# cpu.net
KiCad netlist of a schematic drawn in Altium Designer
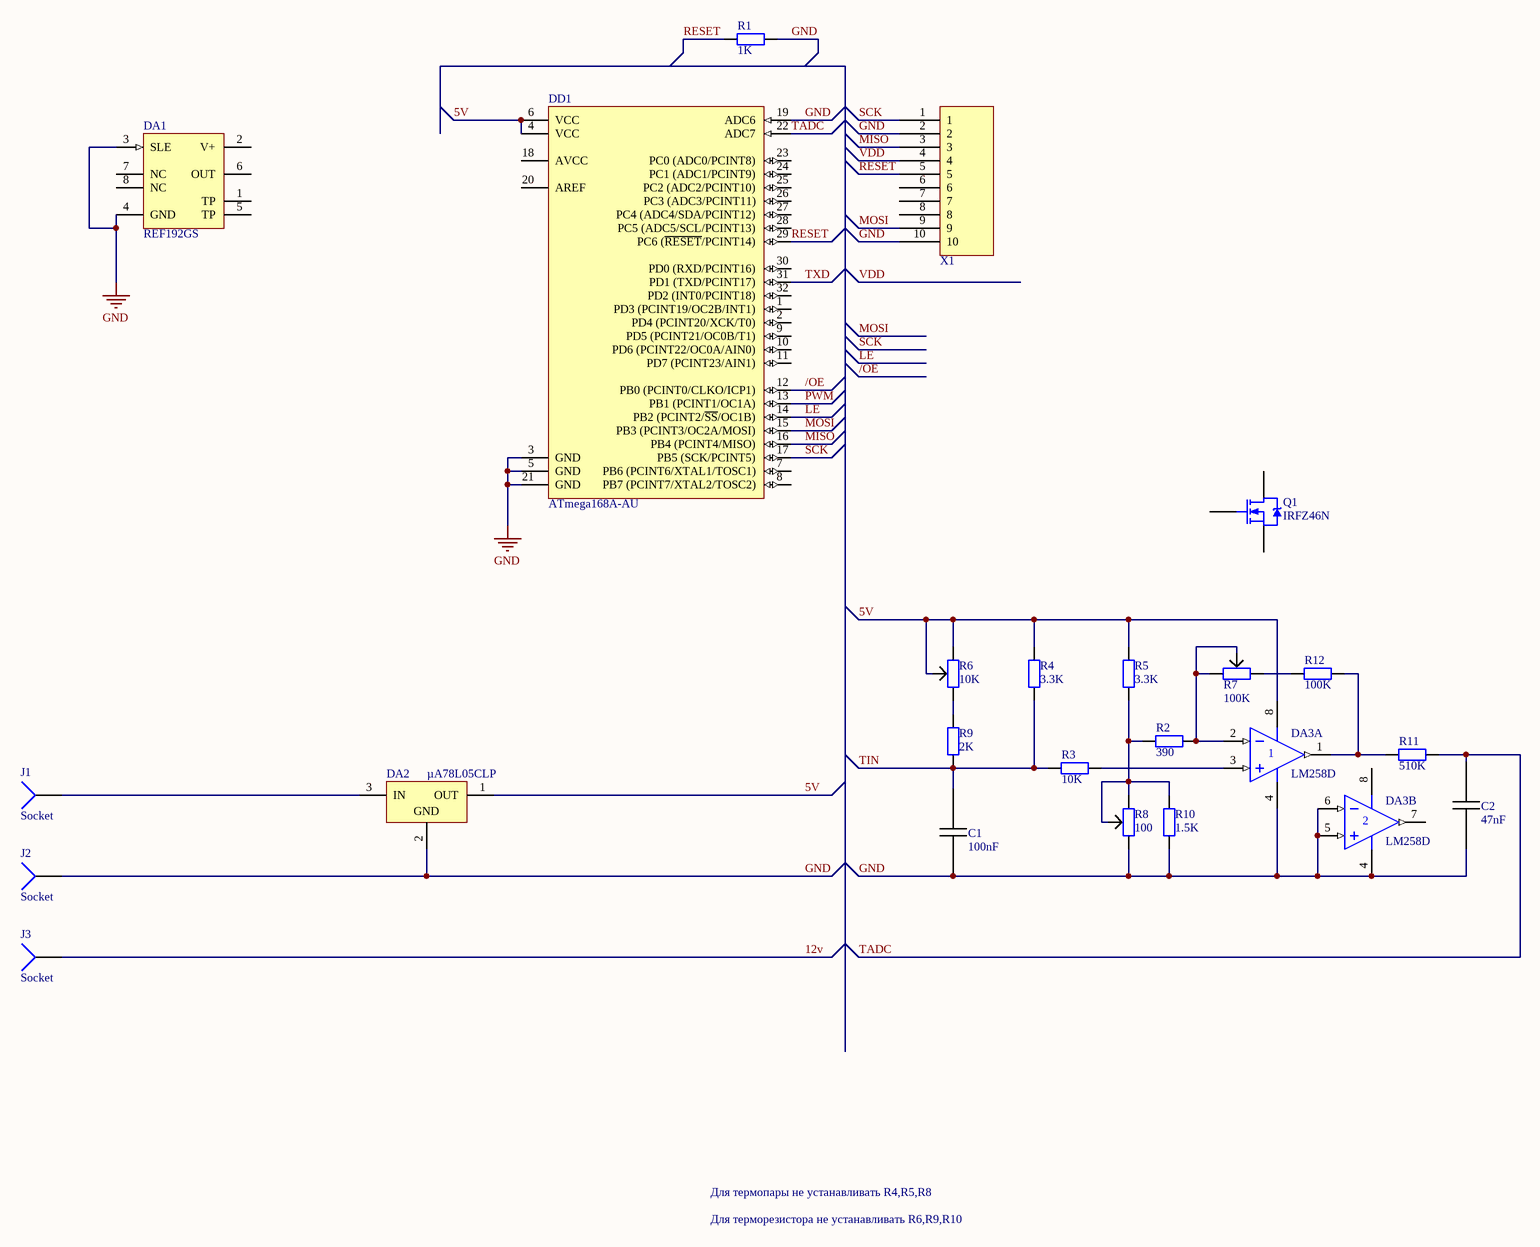
[diagram p0: cpu.SchDoc]

(export (version "E")
  (design (tool "Eeschema 10.0.6"))
  (components
    (comp (ref "C1") (value "100nF") (footprint "R1206") (libsource (lib "Schlib1") (part "cap")))
    (comp (ref "C2") (value "47nF") (footprint "R1206") (libsource (lib "Schlib1") (part "cap")))
    (comp (ref "DA1")
      (value "REF192GS")
      (footprint "SO-8_N")
      (description "2.50V, Precision Micropower, Low-Dropout, Voltage Reference")
      (fields (field (name "PUBLISHER") "Altium Limited"))
      (libsource (lib "AD Power Mgt Voltage Reference") (part "REF192GS"))
    )
    (comp (ref "DA2")
      (value "µA78L05CLP")
      (footprint "LP03")
      (description "Positive-Voltage Regulator")
      (fields (field (name "PUBLISHER") "Altium Limited"))
      (libsource (lib "TI Power Mgt Voltage Regulator") (part "µA78L05CLP"))
    )
    (comp (ref "DA3")
      (value "LM258D")
      (footprint "D008_L")
      (description "Dual Operational Amplifier")
      (fields (field (name "PUBLISHER") "Altium Limited"))
      (libsource (lib "TI Operational Amplifier") (part "LM258D"))
    )
    (comp (ref "DD1")
      (value "ATmega168A-AU")
      (footprint "32A_N")
      (fields (field (name "PUBLISHER") "Altium Limited"))
      (libsource (lib "Atmel Microcontroller 8-Bit megaAVR") (part "ATmega168A-AU"))
    )
    (comp (ref "J1")
      (value "Socket")
      (footprint "PIN1")
      (fields (field (name "PUBLISHER") "Altium Limited"))
      (libsource (lib "Miscellaneous Connectors") (part "Socket"))
    )
    (comp (ref "J2")
      (value "Socket")
      (footprint "PIN1")
      (fields (field (name "PUBLISHER") "Altium Limited"))
      (libsource (lib "Miscellaneous Connectors") (part "Socket"))
    )
    (comp (ref "J3")
      (value "Socket")
      (footprint "PIN1")
      (fields (field (name "PUBLISHER") "Altium Limited"))
      (libsource (lib "Miscellaneous Connectors") (part "Socket"))
    )
    (comp (ref "Q1")
      (value "IRFZ46N")
      (footprint "TO-220AB")
      (description "HEXFET Power MOSFET")
      (fields (field (name "PUBLISHER") "Altium Limited"))
      (libsource (lib "IR Discrete MOSFET - Power") (part "IRFZ46N"))
    )
    (comp (ref "R1") (value "1K") (footprint "PcbLib1:R1206") (libsource (lib "Schlib1") (part "Res")))
    (comp (ref "R2") (value "390") (footprint "PcbLib1:R1206") (libsource (lib "Schlib1") (part "Res")))
    (comp (ref "R3") (value "10K") (footprint "PcbLib1:R1206") (libsource (lib "Schlib1") (part "Res")))
    (comp (ref "R4") (value "3.3K") (footprint "PcbLib1:R1206") (libsource (lib "") (part "Res_2")))
    (comp (ref "R5") (value "3.3K") (footprint "PcbLib1:R1206") (libsource (lib "") (part "Res_2")))
    (comp (ref "R6") (value "10K") (footprint "3296x") (libsource (lib "") (part "RES_P_1")))
    (comp (ref "R7") (value "100K") (footprint "3296x") (libsource (lib "Schlib1") (part "RES_P")))
    (comp (ref "R8") (value "100") (footprint "3296x") (libsource (lib "") (part "RES_P_1")))
    (comp (ref "R9") (value "2K") (footprint "PcbLib1:R1206") (libsource (lib "") (part "Res_2")))
    (comp (ref "R10") (value "1.5K") (footprint "PcbLib1:R1206") (libsource (lib "") (part "Res_2")))
    (comp (ref "R11") (value "510K") (footprint "PcbLib1:R1206") (libsource (lib "") (part "Res_1")))
    (comp (ref "R12") (value "100K") (footprint "PcbLib1:R1206") (libsource (lib "") (part "Res_1")))
    (comp (ref "X1") (value "BHS-10") (footprint "BHS-10") (libsource (lib "Schlib1") (part "BHS-10")))
  )
  (nets
    (net (code "1") (name "/5V") (class "Default")
      (node (ref "DA2") (pin "1") (pinfunction "OUT_1") (pintype "power_in"))
      (node (ref "DA3") (pin "8") (pinfunction "V+_8") (pintype "power_in"))
      (node (ref "DD1") (pin "4") (pinfunction "VCC_4") (pintype "power_in"))
      (node (ref "DD1") (pin "6") (pinfunction "VCC_6") (pintype "power_in"))
      (node (ref "R4") (pin "2") (pinfunction "2_2") (pintype "passive"))
      (node (ref "R5") (pin "2") (pinfunction "2_2") (pintype "passive"))
      (node (ref "R6") (pin "2") (pinfunction "2_2") (pintype "passive"))
      (node (ref "R6") (pin "3") (pinfunction "3_3") (pintype "passive"))
    )
    (net (code "2") (name "/12v") (class "Default")
      (node (ref "J3") (pin "1") (pinfunction "1_1") (pintype "passive"))
    )
    (net (code "3") (name "/LE") (class "Default")
      (node (ref "DD1") (pin "14") (pinfunction "PB2_(PCINT2/~{SS}/OC1B)_14") (pintype "bidirectional"))
    )
    (net (code "4") (name "/MISO") (class "Default")
      (node (ref "DD1") (pin "16") (pinfunction "PB4_(PCINT4/MISO)_16") (pintype "bidirectional"))
      (node (ref "X1") (pin "3") (pinfunction "3_3") (pintype "passive"))
    )
    (net (code "5") (name "/MOSI") (class "Default")
      (node (ref "DD1") (pin "15") (pinfunction "PB3_(PCINT3/OC2A/MOSI)_15") (pintype "bidirectional"))
      (node (ref "X1") (pin "9") (pinfunction "9_9") (pintype "passive"))
    )
    (net (code "6") (name "/PWM") (class "Default")
      (node (ref "DD1") (pin "13") (pinfunction "PB1_(PCINT1/OC1A)_13") (pintype "bidirectional"))
    )
    (net (code "7") (name "/RESET") (class "Default")
      (node (ref "DD1") (pin "29") (pinfunction "PC6_(~{RESET}/PCINT14)_29") (pintype "bidirectional"))
      (node (ref "R1") (pin "1") (pinfunction "1_1") (pintype "passive"))
      (node (ref "X1") (pin "5") (pinfunction "5_5") (pintype "passive"))
    )
    (net (code "8") (name "/SCK") (class "Default")
      (node (ref "DD1") (pin "17") (pinfunction "PB5_(SCK/PCINT5)_17") (pintype "bidirectional"))
      (node (ref "X1") (pin "1") (pinfunction "1_1") (pintype "passive"))
    )
    (net (code "9") (name "/TADC") (class "Default")
      (node (ref "C2") (pin "2") (pinfunction "2_2") (pintype "passive"))
      (node (ref "DD1") (pin "22") (pinfunction "ADC7_22") (pintype "input"))
      (node (ref "R11") (pin "1") (pinfunction "1_1") (pintype "passive"))
    )
    (net (code "10") (name "/TIN") (class "Default")
      (node (ref "C1") (pin "2") (pinfunction "2_2") (pintype "passive"))
      (node (ref "R3") (pin "1") (pinfunction "1_1") (pintype "passive"))
      (node (ref "R4") (pin "1") (pinfunction "1_1") (pintype "passive"))
      (node (ref "R9") (pin "1") (pinfunction "1_1") (pintype "passive"))
    )
    (net (code "11") (name "/TXD") (class "Default")
      (node (ref "DD1") (pin "31") (pinfunction "PD1_(TXD/PCINT17)_31") (pintype "bidirectional"))
    )
    (net (code "12") (name "/VDD") (class "Default")
      (node (ref "X1") (pin "4") (pinfunction "4_4") (pintype "passive"))
    )
    (net (code "13") (name "/{slash}OE") (class "Default")
      (node (ref "DD1") (pin "12") (pinfunction "PB0_(PCINT0/CLKO/ICP1)_12") (pintype "bidirectional"))
    )
    (net (code "14") (name "GND") (class "Default")
      (node (ref "C1") (pin "1") (pinfunction "1_1") (pintype "passive"))
      (node (ref "C2") (pin "1") (pinfunction "1_1") (pintype "passive"))
      (node (ref "DA1") (pin "3") (pinfunction "SLE_3") (pintype "input"))
      (node (ref "DA1") (pin "4") (pinfunction "GND_4") (pintype "power_in"))
      (node (ref "DA2") (pin "2") (pinfunction "GND_2") (pintype "power_in"))
      (node (ref "DA3") (pin "4") (pinfunction "V-_4") (pintype "power_in"))
      (node (ref "DA3") (pin "5") (pinfunction "IN+_5") (pintype "input"))
      (node (ref "DA3") (pin "6") (pinfunction "IN-_6") (pintype "input"))
      (node (ref "DD1") (pin "19") (pinfunction "ADC6_19") (pintype "input"))
      (node (ref "DD1") (pin "21") (pinfunction "GND_21") (pintype "power_in"))
      (node (ref "DD1") (pin "3") (pinfunction "GND_3") (pintype "power_in"))
      (node (ref "DD1") (pin "5") (pinfunction "GND_5") (pintype "power_in"))
      (node (ref "J2") (pin "1") (pinfunction "1_1") (pintype "passive"))
      (node (ref "R1") (pin "2") (pinfunction "2_2") (pintype "passive"))
      (node (ref "R10") (pin "1") (pinfunction "1_1") (pintype "passive"))
      (node (ref "R8") (pin "1") (pinfunction "1_1") (pintype "passive"))
      (node (ref "X1") (pin "10") (pinfunction "10_10") (pintype "passive"))
      (node (ref "X1") (pin "2") (pinfunction "2_2") (pintype "passive"))
    )
    (net (code "15") (name "Net-(DA2-IN)") (class "Default")
      (node (ref "DA2") (pin "3") (pinfunction "IN_3") (pintype "power_in"))
      (node (ref "J1") (pin "1") (pinfunction "1_1") (pintype "passive"))
    )
    (net (code "16") (name "Net-(DA3A-IN+)") (class "Default")
      (node (ref "DA3") (pin "3") (pinfunction "IN+_3") (pintype "input"))
      (node (ref "R3") (pin "2") (pinfunction "2_2") (pintype "passive"))
    )
    (net (code "17") (name "Net-(DA3A-IN-)") (class "Default")
      (node (ref "DA3") (pin "2") (pinfunction "IN-_2") (pintype "input"))
      (node (ref "R2") (pin "2") (pinfunction "2_2") (pintype "passive"))
      (node (ref "R7") (pin "1") (pinfunction "1_1") (pintype "passive"))
      (node (ref "R7") (pin "2") (pinfunction "2_2") (pintype "passive"))
    )
    (net (code "18") (name "Net-(DA3A-OUT)") (class "Default")
      (node (ref "DA3") (pin "1") (pinfunction "OUT_1") (pintype "output"))
      (node (ref "R11") (pin "2") (pinfunction "2_2") (pintype "passive"))
      (node (ref "R12") (pin "1") (pinfunction "1_1") (pintype "passive"))
    )
    (net (code "19") (name "Net-(R6-Pad1)") (class "Default")
      (node (ref "R6") (pin "1") (pinfunction "1_1") (pintype "passive"))
      (node (ref "R9") (pin "2") (pinfunction "2_2") (pintype "passive"))
    )
    (net (code "20") (name "Net-(R10-Pad2)") (class "Default")
      (node (ref "R10") (pin "2") (pinfunction "2_2") (pintype "passive"))
      (node (ref "R2") (pin "1") (pinfunction "1_1") (pintype "passive"))
      (node (ref "R5") (pin "1") (pinfunction "1_1") (pintype "passive"))
      (node (ref "R8") (pin "2") (pinfunction "2_2") (pintype "passive"))
      (node (ref "R8") (pin "3") (pinfunction "3_3") (pintype "passive"))
    )
    (net (code "21") (name "Net-(R12-Pad2)") (class "Default")
      (node (ref "R12") (pin "2") (pinfunction "2_2") (pintype "passive"))
      (node (ref "R7") (pin "3") (pinfunction "3_3") (pintype "passive"))
    )
    (net (code "22") (name "unconnected-(DA1-NC-Pad7)") (class "Default")
      (node (ref "DA1") (pin "7") (pinfunction "NC_7") (pintype "passive"))
    )
    (net (code "23") (name "unconnected-(DA1-NC-Pad8)") (class "Default")
      (node (ref "DA1") (pin "8") (pinfunction "NC_8") (pintype "passive"))
    )
    (net (code "24") (name "unconnected-(DA1-OUT-Pad6)") (class "Default")
      (node (ref "DA1") (pin "6") (pinfunction "OUT_6") (pintype "power_in"))
    )
    (net (code "25") (name "unconnected-(DA1-TP-Pad1)") (class "Default")
      (node (ref "DA1") (pin "1") (pinfunction "TP_1") (pintype "passive"))
    )
    (net (code "26") (name "unconnected-(DA1-TP-Pad5)") (class "Default")
      (node (ref "DA1") (pin "5") (pinfunction "TP_5") (pintype "passive"))
    )
    (net (code "27") (name "unconnected-(DA1-V+-Pad2)") (class "Default")
      (node (ref "DA1") (pin "2") (pinfunction "V+_2") (pintype "power_in"))
    )
    (net (code "28") (name "unconnected-(DA3B-OUT-Pad7)") (class "Default")
      (node (ref "DA3") (pin "7") (pinfunction "OUT_7") (pintype "output"))
    )
    (net (code "29") (name "unconnected-(DA3B-V+-Pad8)") (class "Default")
      (node (ref "DA3") (pin "8") (pinfunction "V+_8") (pintype "power_in"))
    )
    (net (code "30") (name "unconnected-(DD1-AREF-Pad20)") (class "Default")
      (node (ref "DD1") (pin "20") (pinfunction "AREF_20") (pintype "passive"))
    )
    (net (code "31") (name "unconnected-(DD1-AVCC-Pad18)") (class "Default")
      (node (ref "DD1") (pin "18") (pinfunction "AVCC_18") (pintype "power_in"))
    )
    (net (code "32") (name "unconnected-(DD1-PB6_(PCINT6{slash}XTAL1{slash}TOSC1)-Pad7)") (class "Default")
      (node (ref "DD1") (pin "7") (pinfunction "PB6_(PCINT6/XTAL1/TOSC1)_7") (pintype "bidirectional"))
    )
    (net (code "33") (name "unconnected-(DD1-PB7_(PCINT7{slash}XTAL2{slash}TOSC2)-Pad8)") (class "Default")
      (node (ref "DD1") (pin "8") (pinfunction "PB7_(PCINT7/XTAL2/TOSC2)_8") (pintype "bidirectional"))
    )
    (net (code "34") (name "unconnected-(DD1-PC0_(ADC0{slash}PCINT8)-Pad23)") (class "Default")
      (node (ref "DD1") (pin "23") (pinfunction "PC0_(ADC0/PCINT8)_23") (pintype "bidirectional"))
    )
    (net (code "35") (name "unconnected-(DD1-PC1_(ADC1{slash}PCINT9)-Pad24)") (class "Default")
      (node (ref "DD1") (pin "24") (pinfunction "PC1_(ADC1/PCINT9)_24") (pintype "bidirectional"))
    )
    (net (code "36") (name "unconnected-(DD1-PC2_(ADC2{slash}PCINT10)-Pad25)") (class "Default")
      (node (ref "DD1") (pin "25") (pinfunction "PC2_(ADC2/PCINT10)_25") (pintype "bidirectional"))
    )
    (net (code "37") (name "unconnected-(DD1-PC3_(ADC3{slash}PCINT11)-Pad26)") (class "Default")
      (node (ref "DD1") (pin "26") (pinfunction "PC3_(ADC3/PCINT11)_26") (pintype "bidirectional"))
    )
    (net (code "38") (name "unconnected-(DD1-PC4_(ADC4{slash}SDA{slash}PCINT12)-Pad27)") (class "Default")
      (node (ref "DD1") (pin "27") (pinfunction "PC4_(ADC4/SDA/PCINT12)_27") (pintype "bidirectional"))
    )
    (net (code "39") (name "unconnected-(DD1-PC5_(ADC5{slash}SCL{slash}PCINT13)-Pad28)") (class "Default")
      (node (ref "DD1") (pin "28") (pinfunction "PC5_(ADC5/SCL/PCINT13)_28") (pintype "bidirectional"))
    )
    (net (code "40") (name "unconnected-(DD1-PD0_(RXD{slash}PCINT16)-Pad30)") (class "Default")
      (node (ref "DD1") (pin "30") (pinfunction "PD0_(RXD/PCINT16)_30") (pintype "bidirectional"))
    )
    (net (code "41") (name "unconnected-(DD1-PD2_(INT0{slash}PCINT18)-Pad32)") (class "Default")
      (node (ref "DD1") (pin "32") (pinfunction "PD2_(INT0/PCINT18)_32") (pintype "bidirectional"))
    )
    (net (code "42") (name "unconnected-(DD1-PD3_(PCINT19{slash}OC2B{slash}INT1)-Pad1)") (class "Default")
      (node (ref "DD1") (pin "1") (pinfunction "PD3_(PCINT19/OC2B/INT1)_1") (pintype "bidirectional"))
    )
    (net (code "43") (name "unconnected-(DD1-PD4_(PCINT20{slash}XCK{slash}T0)-Pad2)") (class "Default")
      (node (ref "DD1") (pin "2") (pinfunction "PD4_(PCINT20/XCK/T0)_2") (pintype "bidirectional"))
    )
    (net (code "44") (name "unconnected-(DD1-PD5_(PCINT21{slash}OC0B{slash}T1)-Pad9)") (class "Default")
      (node (ref "DD1") (pin "9") (pinfunction "PD5_(PCINT21/OC0B/T1)_9") (pintype "bidirectional"))
    )
    (net (code "45") (name "unconnected-(DD1-PD6_(PCINT22{slash}OC0A{slash}AIN0)-Pad10)") (class "Default")
      (node (ref "DD1") (pin "10") (pinfunction "PD6_(PCINT22/OC0A/AIN0)_10") (pintype "bidirectional"))
    )
    (net (code "46") (name "unconnected-(DD1-PD7_(PCINT23{slash}AIN1)-Pad11)") (class "Default")
      (node (ref "DD1") (pin "11") (pinfunction "PD7_(PCINT23/AIN1)_11") (pintype "bidirectional"))
    )
    (net (code "47") (name "unconnected-(Q1-D-Pad2)") (class "Default")
      (node (ref "Q1") (pin "2") (pinfunction "D_2") (pintype "passive"))
    )
    (net (code "48") (name "unconnected-(Q1-G-Pad1)") (class "Default")
      (node (ref "Q1") (pin "1") (pinfunction "G_1") (pintype "passive"))
    )
    (net (code "49") (name "unconnected-(Q1-S-Pad3)") (class "Default")
      (node (ref "Q1") (pin "3") (pinfunction "S_3") (pintype "passive"))
    )
    (net (code "50") (name "unconnected-(X1-Pad6)") (class "Default")
      (node (ref "X1") (pin "6") (pinfunction "6_6") (pintype "passive"))
    )
    (net (code "51") (name "unconnected-(X1-Pad7)") (class "Default")
      (node (ref "X1") (pin "7") (pinfunction "7_7") (pintype "passive"))
    )
    (net (code "52") (name "unconnected-(X1-Pad8)") (class "Default")
      (node (ref "X1") (pin "8") (pinfunction "8_8") (pintype "passive"))
    )
  )
)
